# Fans.net
KiCad netlist of a schematic drawn in Altium Designer
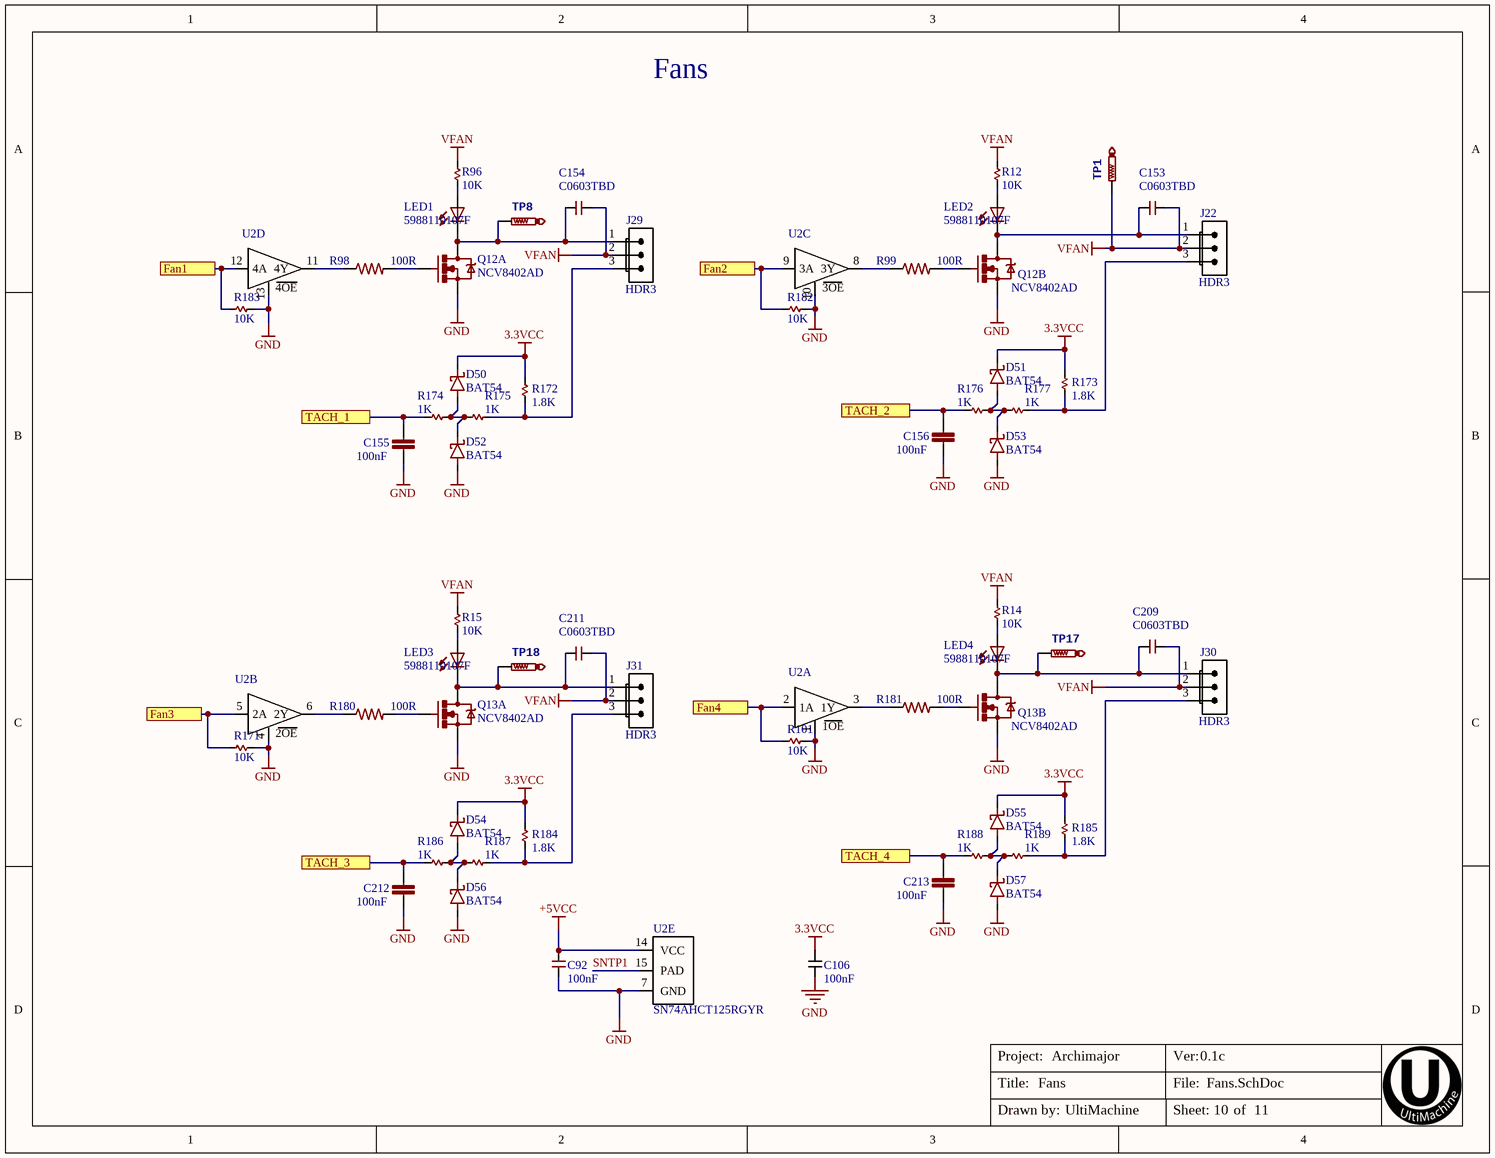
[diagram p0: Fans.SchDoc]

(export (version "E")
  (design (tool "Eeschema 10.0.6"))
  (components
    (comp (ref "C92")
      (value "100nF")
      (footprint "C0402")
      (description "CAP CER 0402 100nF 16V 10% X7R")
      (fields (field (name "MANUFACTURER") "Murata") (field (name "PART") "GRM155R71C104KA88D"))
      (libsource (lib "Capacitors") (part "100nF 0402 16V X7R"))
    )
    (comp (ref "C106")
      (value "100nF")
      (footprint "C0201 Large Pads")
      (description "CAP CER 0.1UF 6.3V 10% X5R 0201")
      (fields (field (name "PART") "CL03A104KQ3NNNC") (field (name "MANUFACTURER") "Samsung"))
      (libsource (lib "Capacitors") (part "100nF 6.3V X5R 0201"))
    )
    (comp (ref "C153")
      (value "C0603TBD")
      (footprint "C0603")
      (description "Capacitor Non Polarized")
      (fields (field (name "PART") "DNI-C0603TBD"))
      (libsource (lib "Capacitors") (part "C0603TBD"))
    )
    (comp (ref "C154")
      (value "C0603TBD")
      (footprint "C0603")
      (description "Capacitor Non Polarized")
      (fields (field (name "PART") "DNI-C0603TBD") (field (name "TOLERANCE") "5%"))
      (libsource (lib "Capacitors") (part "C0603TBD"))
    )
    (comp (ref "C155")
      (value "100nF")
      (footprint "C0402")
      (description "CAP CER 0402 100nF 16V 10% X7R")
      (fields (field (name "MANUFACTURER") "Murata") (field (name "PART") "GRM155R71C104KA88D"))
      (libsource (lib "3Delight") (part "GRM155R71C104KA88D"))
    )
    (comp (ref "C156")
      (value "100nF")
      (footprint "C0402")
      (description "CAP CER 0402 100nF 16V 10% X7R")
      (fields (field (name "MANUFACTURER") "Murata") (field (name "PART") "GRM155R71C104KA88D"))
      (libsource (lib "3Delight") (part "GRM155R71C104KA88D"))
    )
    (comp (ref "C209")
      (value "C0603TBD")
      (footprint "C0603")
      (description "Capacitor Non Polarized")
      (fields (field (name "PART") "DNI-C0603TBD"))
      (libsource (lib "Capacitors") (part "C0603TBD"))
    )
    (comp (ref "C211")
      (value "C0603TBD")
      (footprint "C0603")
      (description "Capacitor Non Polarized")
      (fields (field (name "PART") "DNI-C0603TBD"))
      (libsource (lib "Capacitors") (part "C0603TBD"))
    )
    (comp (ref "C212")
      (value "100nF")
      (footprint "C0402")
      (description "CAP CER 0402 100nF 16V 10% X7R")
      (fields (field (name "MANUFACTURER") "Murata") (field (name "PART") "GRM155R71C104KA88D"))
      (libsource (lib "3Delight") (part "GRM155R71C104KA88D"))
    )
    (comp (ref "C213")
      (value "100nF")
      (footprint "C0402")
      (description "CAP CER 0402 100nF 16V 10% X7R")
      (fields (field (name "MANUFACTURER") "Murata") (field (name "PART") "GRM155R71C104KA88D"))
      (libsource (lib "3Delight") (part "GRM155R71C104KA88D"))
    )
    (comp (ref "D50")
      (value "BAT54")
      (footprint "SOD523_IPC")
      (description "DIODE SCHOTTKY 30V 200MA SOD523")
      (fields (field (name "MANUFACTURER") "Diodes Incorporated") (field (name "PART") "BAT54WX-TP"))
      (libsource (lib "Diodes") (part "BAT54WX"))
    )
    (comp (ref "D51")
      (value "BAT54")
      (footprint "SOD523_IPC")
      (description "DIODE SCHOTTKY 30V 200MA SOD523")
      (fields (field (name "MANUFACTURER") "Diodes Incorporated") (field (name "PART") "BAT54WX-TP"))
      (libsource (lib "Diodes") (part "BAT54WX"))
    )
    (comp (ref "D52")
      (value "BAT54")
      (footprint "SOD523_IPC")
      (description "DIODE SCHOTTKY 30V 200MA SOD523")
      (fields (field (name "MANUFACTURER") "Diodes Incorporated") (field (name "PART") "BAT54WX-TP"))
      (libsource (lib "Diodes") (part "BAT54WX"))
    )
    (comp (ref "D53")
      (value "BAT54")
      (footprint "SOD523_IPC")
      (description "DIODE SCHOTTKY 30V 200MA SOD523")
      (fields (field (name "MANUFACTURER") "Diodes Incorporated") (field (name "PART") "BAT54WX-TP"))
      (libsource (lib "Diodes") (part "BAT54WX"))
    )
    (comp (ref "D54")
      (value "BAT54")
      (footprint "SOD523_IPC")
      (description "DIODE SCHOTTKY 30V 200MA SOD523")
      (fields (field (name "MANUFACTURER") "Diodes Incorporated") (field (name "PART") "BAT54WX-TP"))
      (libsource (lib "Diodes") (part "BAT54WX"))
    )
    (comp (ref "D55")
      (value "BAT54")
      (footprint "SOD523_IPC")
      (description "DIODE SCHOTTKY 30V 200MA SOD523")
      (fields (field (name "MANUFACTURER") "Diodes Incorporated") (field (name "PART") "BAT54WX-TP"))
      (libsource (lib "Diodes") (part "BAT54WX"))
    )
    (comp (ref "D56")
      (value "BAT54")
      (footprint "SOD523_IPC")
      (description "DIODE SCHOTTKY 30V 200MA SOD523")
      (fields (field (name "MANUFACTURER") "Diodes Incorporated") (field (name "PART") "BAT54WX-TP"))
      (libsource (lib "Diodes") (part "BAT54WX"))
    )
    (comp (ref "D57")
      (value "BAT54")
      (footprint "SOD523_IPC")
      (description "DIODE SCHOTTKY 30V 200MA SOD523")
      (fields (field (name "MANUFACTURER") "Diodes Incorporated") (field (name "PART") "BAT54WX-TP"))
      (libsource (lib "Diodes") (part "BAT54WX"))
    )
    (comp (ref "J22")
      (value "HDR3")
      (footprint "70543-02 PIN-IN-PASTE")
      (description "3 Positions Header, Shrouded Connector 0.100\" (2.54mm) Through Hole Gold - Pin in Paste")
      (fields (field (name "MANUFACTURER") "Molex") (field (name "PART") "0705430002"))
      (libsource (lib "Connectors") (part "CONN 3POS VERT 0.1{dblquote} SHRD LOCKING PIP"))
    )
    (comp (ref "J29")
      (value "HDR3")
      (footprint "70543-02 PIN-IN-PASTE")
      (description "3 Positions Header, Shrouded Connector 0.100\" (2.54mm) Through Hole Gold - Pin in Paste")
      (fields (field (name "MANUFACTURER") "Molex") (field (name "PART") "0705430002"))
      (libsource (lib "Connectors") (part "CONN 3POS VERT 0.1{dblquote} SHRD LOCKING PIP"))
    )
    (comp (ref "J30")
      (value "HDR3")
      (footprint "70543-02 PIN-IN-PASTE")
      (description "3 Positions Header, Shrouded Connector 0.100\" (2.54mm) Through Hole Gold - Pin in Paste")
      (fields (field (name "MANUFACTURER") "Molex") (field (name "PART") "0705430002"))
      (libsource (lib "Connectors") (part "CONN 3POS VERT 0.1{dblquote} SHRD LOCKING PIP"))
    )
    (comp (ref "J31")
      (value "HDR3")
      (footprint "70543-02 PIN-IN-PASTE")
      (description "3 Positions Header, Shrouded Connector 0.100\" (2.54mm) Through Hole Gold - Pin in Paste")
      (fields (field (name "MANUFACTURER") "Molex") (field (name "PART") "0705430002"))
      (libsource (lib "Connectors") (part "CONN 3POS VERT 0.1{dblquote} SHRD LOCKING PIP"))
    )
    (comp (ref "LED1")
      (value "RED")
      (footprint "LED2012120")
      (description "LED 0805 Red")
      (fields
        (field (name "MANUFACTURER") "Dialight")
        (field (name "PART") "5988110107F")
        (field (name "TOLERANCE") "NA")
      )
      (libsource (lib "3Delight") (part "5988110107F"))
    )
    (comp (ref "LED2")
      (value "RED")
      (footprint "LED2012120")
      (description "LED 0805 Red")
      (fields
        (field (name "MANUFACTURER") "Dialight")
        (field (name "PART") "5988110107F")
        (field (name "TOLERANCE") "NA")
      )
      (libsource (lib "3Delight") (part "5988110107F"))
    )
    (comp (ref "LED3")
      (value "RED")
      (footprint "LED2012120")
      (description "LED 0805 Red")
      (fields
        (field (name "MANUFACTURER") "Dialight")
        (field (name "PART") "5988110107F")
        (field (name "TOLERANCE") "NA")
      )
      (libsource (lib "3Delight") (part "5988110107F"))
    )
    (comp (ref "LED4")
      (value "RED")
      (footprint "LED2012120")
      (description "LED 0805 Red")
      (fields
        (field (name "MANUFACTURER") "Dialight")
        (field (name "PART") "5988110107F")
        (field (name "TOLERANCE") "NA")
      )
      (libsource (lib "3Delight") (part "5988110107F"))
    )
    (comp (ref "Q12")
      (value "NCV8402AD")
      (footprint "NCV8402AD-SOIC8")
      (description "IC DVR LOW SIDE 8-SOIC")
      (fields (field (name "MANUFACTURER") "On Semi") (field (name "PART") "NCV8402ADDR2G"))
      (libsource (lib "Transistors") (part "NCV8402AD"))
    )
    (comp (ref "Q13")
      (value "NCV8402AD")
      (footprint "NCV8402AD-SOIC8")
      (description "IC DVR LOW SIDE 8-SOIC")
      (fields (field (name "MANUFACTURER") "On Semi") (field (name "PART") "NCV8402ADDR2G"))
      (libsource (lib "Transistors") (part "NCV8402AD"))
    )
    (comp (ref "R12")
      (value "10K")
      (footprint "R0402")
      (description "RES SMD 10K OHM 1% 1/16W 0402")
      (fields (field (name "MANUFACTURER") "Yageo") (field (name "PART") "RC0402FR-0710KP"))
      (libsource (lib "Resistors") (part "10k 1% 0402"))
    )
    (comp (ref "R14")
      (value "10K")
      (footprint "R0402")
      (description "RES SMD 10K OHM 1% 1/16W 0402")
      (fields (field (name "MANUFACTURER") "Yageo") (field (name "PART") "RC0402FR-0710KP"))
      (libsource (lib "Resistors") (part "10k 1% 0402"))
    )
    (comp (ref "R15")
      (value "10K")
      (footprint "R0402")
      (description "RES SMD 10K OHM 1% 1/16W 0402")
      (fields (field (name "MANUFACTURER") "Yageo") (field (name "PART") "RC0402FR-0710KP"))
      (libsource (lib "Resistors") (part "10k 1% 0402"))
    )
    (comp (ref "R96")
      (value "10K")
      (footprint "R0402")
      (description "RES SMD 10K OHM 1% 1/16W 0402")
      (fields (field (name "MANUFACTURER") "Yageo") (field (name "PART") "RC0402FR-0710KP"))
      (libsource (lib "Resistors") (part "10k 1% 0402"))
    )
    (comp (ref "R98")
      (value "100R")
      (footprint "R0402")
      (description "RES SMD 100 OHM 1% 1/16W 0402")
      (fields (field (name "MANUFACTURER") "Yageo") (field (name "PART") "RC0402FR-07100RL"))
      (libsource (lib "Archim") (part "RES 100R 0402 1%"))
    )
    (comp (ref "R99")
      (value "100R")
      (footprint "R0402")
      (description "RES SMD 100 OHM 1% 1/16W 0402")
      (fields (field (name "MANUFACTURER") "Yageo") (field (name "PART") "RC0402FR-07100RL"))
      (libsource (lib "Archim") (part "RES 100R 0402 1%"))
    )
    (comp (ref "R101")
      (value "10K")
      (footprint "R0402")
      (description "RES SMD 10K OHM 1% 1/16W 0402")
      (fields (field (name "MANUFACTURER") "Yageo") (field (name "PART") "RC0402FR-0710KP"))
      (libsource (lib "Resistors") (part "10k 1% 0402"))
    )
    (comp (ref "R171")
      (value "10K")
      (footprint "R0402")
      (description "RES SMD 10K OHM 1% 1/16W 0402")
      (fields (field (name "MANUFACTURER") "Yageo") (field (name "PART") "RC0402FR-0710KP"))
      (libsource (lib "Resistors") (part "10k 1% 0402"))
    )
    (comp (ref "R172")
      (value "1.8K")
      (footprint "R0402")
      (description "RES SMD 1.8K OHM 1% 1/16W 0402")
      (fields (field (name "MANUFACTURER") "Yageo") (field (name "PART") "RC0402FR-071K8L"))
      (libsource (lib "3Delight") (part "RC0402FR-071K8L"))
    )
    (comp (ref "R173")
      (value "1.8K")
      (footprint "R0402")
      (description "RES SMD 1.8K OHM 1% 1/16W 0402")
      (fields (field (name "MANUFACTURER") "Yageo") (field (name "PART") "RC0402FR-071K8L"))
      (libsource (lib "3Delight") (part "RC0402FR-071K8L"))
    )
    (comp (ref "R174")
      (value "1K")
      (footprint "R0402")
      (description "RES SMD 1K OHM 1% 1/16W 0402")
      (fields (field (name "MANUFACTURER") "Yageo") (field (name "PART") "RC0402FR-071KL"))
      (libsource (lib "3Delight") (part "RC0402FR-071KL"))
    )
    (comp (ref "R175")
      (value "1K")
      (footprint "R0402")
      (description "RES SMD 1K OHM 1% 1/16W 0402")
      (fields (field (name "MANUFACTURER") "Yageo") (field (name "PART") "RC0402FR-071KL"))
      (libsource (lib "3Delight") (part "RC0402FR-071KL"))
    )
    (comp (ref "R176")
      (value "1K")
      (footprint "R0402")
      (description "RES SMD 1K OHM 1% 1/16W 0402")
      (fields (field (name "MANUFACTURER") "Yageo") (field (name "PART") "RC0402FR-071KL"))
      (libsource (lib "3Delight") (part "RC0402FR-071KL"))
    )
    (comp (ref "R177")
      (value "1K")
      (footprint "R0402")
      (description "RES SMD 1K OHM 1% 1/16W 0402")
      (fields (field (name "MANUFACTURER") "Yageo") (field (name "PART") "RC0402FR-071KL"))
      (libsource (lib "3Delight") (part "RC0402FR-071KL"))
    )
    (comp (ref "R180")
      (value "100R")
      (footprint "R0402")
      (description "RES SMD 100 OHM 1% 1/16W 0402")
      (fields (field (name "MANUFACTURER") "Yageo") (field (name "PART") "RC0402FR-07100RL"))
      (libsource (lib "Archim") (part "RES 100R 0402 1%"))
    )
    (comp (ref "R181")
      (value "100R")
      (footprint "R0402")
      (description "RES SMD 100 OHM 1% 1/16W 0402")
      (fields (field (name "MANUFACTURER") "Yageo") (field (name "PART") "RC0402FR-07100RL"))
      (libsource (lib "Archim") (part "RES 100R 0402 1%"))
    )
    (comp (ref "R182")
      (value "10K")
      (footprint "R0402")
      (description "RES SMD 10K OHM 1% 1/16W 0402")
      (fields (field (name "MANUFACTURER") "Yageo") (field (name "PART") "RC0402FR-0710KP"))
      (libsource (lib "Resistors") (part "10k 1% 0402"))
    )
    (comp (ref "R183")
      (value "10K")
      (footprint "R0402")
      (description "RES SMD 10K OHM 1% 1/16W 0402")
      (fields (field (name "MANUFACTURER") "Yageo") (field (name "PART") "RC0402FR-0710KP"))
      (libsource (lib "Resistors") (part "10k 1% 0402"))
    )
    (comp (ref "R184")
      (value "1.8K")
      (footprint "R0402")
      (description "RES SMD 1.8K OHM 1% 1/16W 0402")
      (fields (field (name "MANUFACTURER") "Yageo") (field (name "PART") "RC0402FR-071K8L"))
      (libsource (lib "3Delight") (part "RC0402FR-071K8L"))
    )
    (comp (ref "R185")
      (value "1.8K")
      (footprint "R0402")
      (description "RES SMD 1.8K OHM 1% 1/16W 0402")
      (fields (field (name "MANUFACTURER") "Yageo") (field (name "PART") "RC0402FR-071K8L"))
      (libsource (lib "3Delight") (part "RC0402FR-071K8L"))
    )
    (comp (ref "R186")
      (value "1K")
      (footprint "R0402")
      (description "RES SMD 1K OHM 1% 1/16W 0402")
      (fields (field (name "MANUFACTURER") "Yageo") (field (name "PART") "RC0402FR-071KL"))
      (libsource (lib "3Delight") (part "RC0402FR-071KL"))
    )
    (comp (ref "R187")
      (value "1K")
      (footprint "R0402")
      (description "RES SMD 1K OHM 1% 1/16W 0402")
      (fields (field (name "MANUFACTURER") "Yageo") (field (name "PART") "RC0402FR-071KL"))
      (libsource (lib "3Delight") (part "RC0402FR-071KL"))
    )
    (comp (ref "R188")
      (value "1K")
      (footprint "R0402")
      (description "RES SMD 1K OHM 1% 1/16W 0402")
      (fields (field (name "MANUFACTURER") "Yageo") (field (name "PART") "RC0402FR-071KL"))
      (libsource (lib "3Delight") (part "RC0402FR-071KL"))
    )
    (comp (ref "R189")
      (value "1K")
      (footprint "R0402")
      (description "RES SMD 1K OHM 1% 1/16W 0402")
      (fields (field (name "MANUFACTURER") "Yageo") (field (name "PART") "RC0402FR-071KL"))
      (libsource (lib "3Delight") (part "RC0402FR-071KL"))
    )
    (comp (ref "TP1")
      (value "TestPoint")
      (footprint "TP1-27")
      (description "Test Point")
      (libsource (lib "3Delight") (part "TestPoint"))
    )
    (comp (ref "TP8")
      (value "TestPoint")
      (footprint "TP1-27")
      (description "Test Point")
      (libsource (lib "") (part "TestPoint_1"))
    )
    (comp (ref "TP17")
      (value "TestPoint")
      (footprint "TP1-27")
      (description "Test Point")
      (libsource (lib "") (part "TestPoint_1"))
    )
    (comp (ref "TP18")
      (value "TestPoint")
      (footprint "TP1-27")
      (description "Test Point")
      (libsource (lib "") (part "TestPoint_1"))
    )
    (comp (ref "U2")
      (value "SN74AHCT125RGYR")
      (footprint "QFN50P350X350X100_RGY_S-PVQFN-N14")
      (description "Quadruple Bus Buffer Gates With 3-State Outputs 14-VQFN -40 to 125")
      (fields (field (name "MANUFACTURER") "Texas Instruments") (field (name "TOLERANCE") "-NA-"))
      (libsource (lib "ICs-Logic") (part "SN74AHCT125"))
    )
  )
  (nets
    (net (code "1") (name "+5VCC") (class "Default")
      (node (ref "C92") (pin "2") (pinfunction "2_2") (pintype "passive"))
      (node (ref "U2") (pin "14") (pinfunction "VCC_14") (pintype "passive"))
    )
    (net (code "2") (name "/Fan1") (class "Default")
      (node (ref "R183") (pin "1") (pinfunction "1_1") (pintype "passive"))
      (node (ref "U2") (pin "12") (pinfunction "4A_12") (pintype "passive"))
    )
    (net (code "3") (name "/Fan2") (class "Default")
      (node (ref "R182") (pin "1") (pinfunction "1_1") (pintype "passive"))
      (node (ref "U2") (pin "9") (pinfunction "3A_9") (pintype "passive"))
    )
    (net (code "4") (name "/Fan3") (class "Default")
      (node (ref "R171") (pin "1") (pinfunction "1_1") (pintype "passive"))
      (node (ref "U2") (pin "5") (pinfunction "2A_5") (pintype "passive"))
    )
    (net (code "5") (name "/Fan4") (class "Default")
      (node (ref "R101") (pin "1") (pinfunction "1_1") (pintype "passive"))
      (node (ref "U2") (pin "2") (pinfunction "1A_2") (pintype "passive"))
    )
    (net (code "6") (name "/SNTP1") (class "Default")
      (node (ref "U2") (pin "15") (pinfunction "PAD_15") (pintype "passive"))
    )
    (net (code "7") (name "/TACH_1") (class "Default")
      (node (ref "C155") (pin "1") (pinfunction "1_1") (pintype "passive"))
      (node (ref "R174") (pin "1") (pinfunction "1_1") (pintype "passive"))
    )
    (net (code "8") (name "/TACH_2") (class "Default")
      (node (ref "C156") (pin "1") (pinfunction "1_1") (pintype "passive"))
      (node (ref "R176") (pin "1") (pinfunction "1_1") (pintype "passive"))
    )
    (net (code "9") (name "/TACH_3") (class "Default")
      (node (ref "C212") (pin "1") (pinfunction "1_1") (pintype "passive"))
      (node (ref "R186") (pin "1") (pinfunction "1_1") (pintype "passive"))
    )
    (net (code "10") (name "/TACH_4") (class "Default")
      (node (ref "C213") (pin "1") (pinfunction "1_1") (pintype "passive"))
      (node (ref "R188") (pin "1") (pinfunction "1_1") (pintype "passive"))
    )
    (net (code "11") (name "3.3VCC") (class "Default")
      (node (ref "C106") (pin "2") (pinfunction "2_2") (pintype "passive"))
      (node (ref "D50") (pin "K") (pinfunction "K_K") (pintype "passive"))
      (node (ref "D51") (pin "K") (pinfunction "K_K") (pintype "passive"))
      (node (ref "D54") (pin "K") (pinfunction "K_K") (pintype "passive"))
      (node (ref "D55") (pin "K") (pinfunction "K_K") (pintype "passive"))
      (node (ref "R172") (pin "2") (pinfunction "2_2") (pintype "passive"))
      (node (ref "R173") (pin "2") (pinfunction "2_2") (pintype "passive"))
      (node (ref "R184") (pin "2") (pinfunction "2_2") (pintype "passive"))
      (node (ref "R185") (pin "2") (pinfunction "2_2") (pintype "passive"))
    )
    (net (code "12") (name "GND") (class "Default")
      (node (ref "C106") (pin "1") (pinfunction "1_1") (pintype "passive"))
      (node (ref "C155") (pin "2") (pinfunction "2_2") (pintype "passive"))
      (node (ref "C156") (pin "2") (pinfunction "2_2") (pintype "passive"))
      (node (ref "C212") (pin "2") (pinfunction "2_2") (pintype "passive"))
      (node (ref "C213") (pin "2") (pinfunction "2_2") (pintype "passive"))
      (node (ref "C92") (pin "1") (pinfunction "1_1") (pintype "passive"))
      (node (ref "D52") (pin "A") (pinfunction "A_A") (pintype "passive"))
      (node (ref "D56") (pin "A") (pinfunction "A_A") (pintype "passive"))
      (node (ref "D57") (pin "A") (pinfunction "A_A") (pintype "passive"))
      (node (ref "Q12") (pin "1") (pinfunction "S_1") (pintype "passive"))
      (node (ref "Q12") (pin "3") (pinfunction "S_3") (pintype "passive"))
      (node (ref "Q13") (pin "1") (pinfunction "S_1") (pintype "passive"))
      (node (ref "Q13") (pin "3") (pinfunction "S_3") (pintype "passive"))
      (node (ref "R101") (pin "2") (pinfunction "2_2") (pintype "passive"))
      (node (ref "R171") (pin "2") (pinfunction "2_2") (pintype "passive"))
      (node (ref "R182") (pin "2") (pinfunction "2_2") (pintype "passive"))
      (node (ref "R183") (pin "2") (pinfunction "2_2") (pintype "passive"))
      (node (ref "U2") (pin "1") (pinfunction "1OE_1") (pintype "passive"))
      (node (ref "U2") (pin "10") (pinfunction "3OE_10") (pintype "passive"))
      (node (ref "U2") (pin "13") (pinfunction "4OE_13") (pintype "passive"))
      (node (ref "U2") (pin "4") (pinfunction "2OE_4") (pintype "passive"))
      (node (ref "U2") (pin "7") (pinfunction "GND_7") (pintype "passive"))
    )
    (net (code "13") (name "Net-(D50-PadA)") (class "Default")
      (node (ref "D50") (pin "A") (pinfunction "A_A") (pintype "passive"))
      (node (ref "D52") (pin "K") (pinfunction "K_K") (pintype "passive"))
      (node (ref "R174") (pin "2") (pinfunction "2_2") (pintype "passive"))
      (node (ref "R175") (pin "1") (pinfunction "1_1") (pintype "passive"))
    )
    (net (code "14") (name "Net-(D51-PadA)") (class "Default")
      (node (ref "D51") (pin "A") (pinfunction "A_A") (pintype "passive"))
      (node (ref "D53") (pin "K") (pinfunction "K_K") (pintype "passive"))
      (node (ref "R176") (pin "2") (pinfunction "2_2") (pintype "passive"))
      (node (ref "R177") (pin "1") (pinfunction "1_1") (pintype "passive"))
    )
    (net (code "15") (name "Net-(D54-PadA)") (class "Default")
      (node (ref "D54") (pin "A") (pinfunction "A_A") (pintype "passive"))
      (node (ref "D56") (pin "K") (pinfunction "K_K") (pintype "passive"))
      (node (ref "R186") (pin "2") (pinfunction "2_2") (pintype "passive"))
      (node (ref "R187") (pin "1") (pinfunction "1_1") (pintype "passive"))
    )
    (net (code "16") (name "Net-(D55-PadA)") (class "Default")
      (node (ref "D55") (pin "A") (pinfunction "A_A") (pintype "passive"))
      (node (ref "D57") (pin "K") (pinfunction "K_K") (pintype "passive"))
      (node (ref "R188") (pin "2") (pinfunction "2_2") (pintype "passive"))
      (node (ref "R189") (pin "1") (pinfunction "1_1") (pintype "passive"))
    )
    (net (code "17") (name "Net-(J22-S-Pad3)") (class "Default")
      (node (ref "J22") (pin "3") (pinfunction "S_3") (pintype "passive"))
      (node (ref "R173") (pin "1") (pinfunction "1_1") (pintype "passive"))
      (node (ref "R177") (pin "2") (pinfunction "2_2") (pintype "passive"))
    )
    (net (code "18") (name "Net-(J29-S-Pad3)") (class "Default")
      (node (ref "J29") (pin "3") (pinfunction "S_3") (pintype "passive"))
      (node (ref "R172") (pin "1") (pinfunction "1_1") (pintype "passive"))
      (node (ref "R175") (pin "2") (pinfunction "2_2") (pintype "passive"))
    )
    (net (code "19") (name "Net-(J30-S-Pad3)") (class "Default")
      (node (ref "J30") (pin "3") (pinfunction "S_3") (pintype "passive"))
      (node (ref "R185") (pin "1") (pinfunction "1_1") (pintype "passive"))
      (node (ref "R189") (pin "2") (pinfunction "2_2") (pintype "passive"))
    )
    (net (code "20") (name "Net-(J31-S-Pad3)") (class "Default")
      (node (ref "J31") (pin "3") (pinfunction "S_3") (pintype "passive"))
      (node (ref "R184") (pin "1") (pinfunction "1_1") (pintype "passive"))
      (node (ref "R187") (pin "2") (pinfunction "2_2") (pintype "passive"))
    )
    (net (code "21") (name "Net-(LED1-PadA)") (class "Default")
      (node (ref "LED1") (pin "A") (pinfunction "A_A") (pintype "passive"))
      (node (ref "R96") (pin "1") (pinfunction "1_1") (pintype "passive"))
    )
    (net (code "22") (name "Net-(LED2-PadA)") (class "Default")
      (node (ref "LED2") (pin "A") (pinfunction "A_A") (pintype "passive"))
      (node (ref "R12") (pin "1") (pinfunction "1_1") (pintype "passive"))
    )
    (net (code "23") (name "Net-(LED3-PadA)") (class "Default")
      (node (ref "LED3") (pin "A") (pinfunction "A_A") (pintype "passive"))
      (node (ref "R15") (pin "1") (pinfunction "1_1") (pintype "passive"))
    )
    (net (code "24") (name "Net-(LED4-PadA)") (class "Default")
      (node (ref "LED4") (pin "A") (pinfunction "A_A") (pintype "passive"))
      (node (ref "R14") (pin "1") (pinfunction "1_1") (pintype "passive"))
    )
    (net (code "25") (name "Net-(Q12A-D)") (class "Default")
      (node (ref "C154") (pin "2") (pinfunction "2_2") (pintype "passive"))
      (node (ref "J29") (pin "1") (pinfunction "S_1") (pintype "passive"))
      (node (ref "LED1") (pin "C") (pinfunction "C_C") (pintype "passive"))
      (node (ref "Q12") (pin "7") (pinfunction "D_7") (pintype "passive"))
      (node (ref "TP8") (pin "TP") (pinfunction "TP_TP") (pintype "passive"))
    )
    (net (code "26") (name "Net-(Q12A-G)") (class "Default")
      (node (ref "Q12") (pin "2") (pinfunction "G_2") (pintype "passive"))
      (node (ref "R98") (pin "2") (pinfunction "2_2") (pintype "passive"))
    )
    (net (code "27") (name "Net-(Q12B-D)") (class "Default")
      (node (ref "C153") (pin "2") (pinfunction "2_2") (pintype "passive"))
      (node (ref "J22") (pin "1") (pinfunction "S_1") (pintype "passive"))
      (node (ref "LED2") (pin "C") (pinfunction "C_C") (pintype "passive"))
      (node (ref "Q12") (pin "5") (pinfunction "D_5") (pintype "passive"))
    )
    (net (code "28") (name "Net-(Q12B-G)") (class "Default")
      (node (ref "Q12") (pin "4") (pinfunction "G_4") (pintype "passive"))
      (node (ref "R99") (pin "2") (pinfunction "2_2") (pintype "passive"))
    )
    (net (code "29") (name "Net-(Q13A-D)") (class "Default")
      (node (ref "C211") (pin "2") (pinfunction "2_2") (pintype "passive"))
      (node (ref "J31") (pin "1") (pinfunction "S_1") (pintype "passive"))
      (node (ref "LED3") (pin "C") (pinfunction "C_C") (pintype "passive"))
      (node (ref "Q13") (pin "7") (pinfunction "D_7") (pintype "passive"))
      (node (ref "TP18") (pin "TP") (pinfunction "TP_TP") (pintype "passive"))
    )
    (net (code "30") (name "Net-(Q13A-G)") (class "Default")
      (node (ref "Q13") (pin "2") (pinfunction "G_2") (pintype "passive"))
      (node (ref "R180") (pin "2") (pinfunction "2_2") (pintype "passive"))
    )
    (net (code "31") (name "Net-(Q13B-D)") (class "Default")
      (node (ref "C209") (pin "2") (pinfunction "2_2") (pintype "passive"))
      (node (ref "J30") (pin "1") (pinfunction "S_1") (pintype "passive"))
      (node (ref "LED4") (pin "C") (pinfunction "C_C") (pintype "passive"))
      (node (ref "Q13") (pin "5") (pinfunction "D_5") (pintype "passive"))
      (node (ref "TP17") (pin "TP") (pinfunction "TP_TP") (pintype "passive"))
    )
    (net (code "32") (name "Net-(Q13B-G)") (class "Default")
      (node (ref "Q13") (pin "4") (pinfunction "G_4") (pintype "passive"))
      (node (ref "R181") (pin "2") (pinfunction "2_2") (pintype "passive"))
    )
    (net (code "33") (name "Net-(U2A-1Y)") (class "Default")
      (node (ref "R181") (pin "1") (pinfunction "1_1") (pintype "passive"))
      (node (ref "U2") (pin "3") (pinfunction "1Y_3") (pintype "passive"))
    )
    (net (code "34") (name "Net-(U2B-2Y)") (class "Default")
      (node (ref "R180") (pin "1") (pinfunction "1_1") (pintype "passive"))
      (node (ref "U2") (pin "6") (pinfunction "2Y_6") (pintype "passive"))
    )
    (net (code "35") (name "Net-(U2C-3Y)") (class "Default")
      (node (ref "R99") (pin "1") (pinfunction "1_1") (pintype "passive"))
      (node (ref "U2") (pin "8") (pinfunction "3Y_8") (pintype "passive"))
    )
    (net (code "36") (name "Net-(U2D-4Y)") (class "Default")
      (node (ref "R98") (pin "1") (pinfunction "1_1") (pintype "passive"))
      (node (ref "U2") (pin "11") (pinfunction "4Y_11") (pintype "passive"))
    )
    (net (code "37") (name "VFAN") (class "Default")
      (node (ref "C153") (pin "1") (pinfunction "1_1") (pintype "passive"))
      (node (ref "C154") (pin "1") (pinfunction "1_1") (pintype "passive"))
      (node (ref "C209") (pin "1") (pinfunction "1_1") (pintype "passive"))
      (node (ref "C211") (pin "1") (pinfunction "1_1") (pintype "passive"))
      (node (ref "J22") (pin "2") (pinfunction "S_2") (pintype "passive"))
      (node (ref "J29") (pin "2") (pinfunction "S_2") (pintype "passive"))
      (node (ref "J30") (pin "2") (pinfunction "S_2") (pintype "passive"))
      (node (ref "J31") (pin "2") (pinfunction "S_2") (pintype "passive"))
      (node (ref "R12") (pin "2") (pinfunction "2_2") (pintype "passive"))
      (node (ref "R14") (pin "2") (pinfunction "2_2") (pintype "passive"))
      (node (ref "R15") (pin "2") (pinfunction "2_2") (pintype "passive"))
      (node (ref "R96") (pin "2") (pinfunction "2_2") (pintype "passive"))
      (node (ref "TP1") (pin "TP") (pinfunction "TP_TP") (pintype "passive"))
    )
    (net (code "38") (name "unconnected-(D53-PadA)") (class "Default")
      (node (ref "D53") (pin "A") (pinfunction "A_A") (pintype "passive"))
    )
  )
)
